# Control_Board.net
KiCad netlist of a schematic drawn in EAGLE
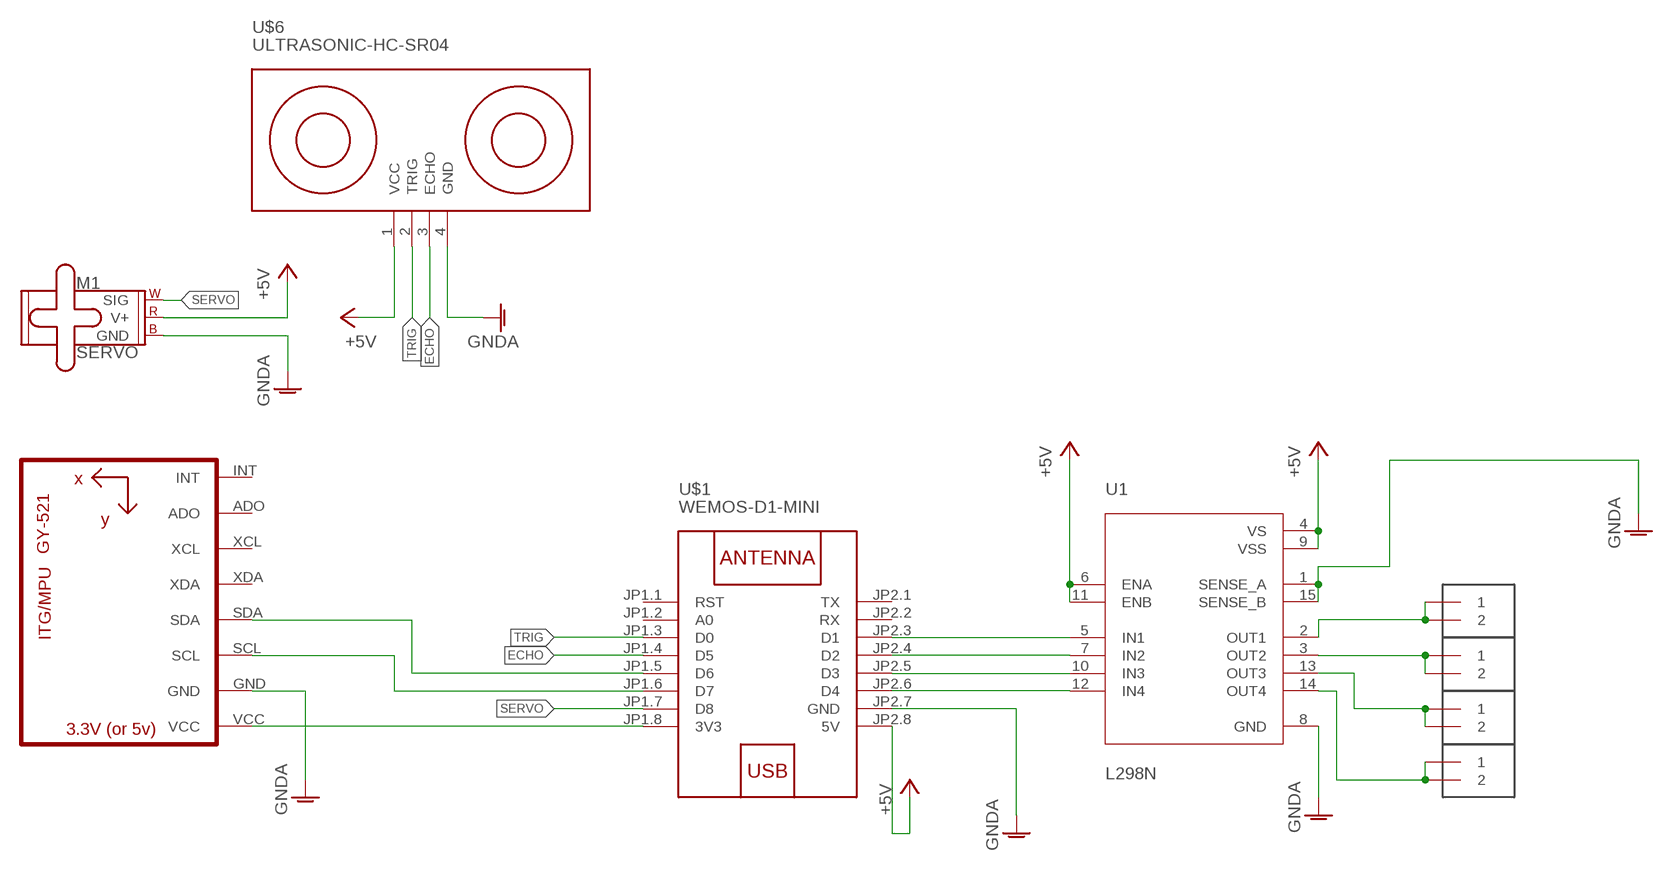
[diagram p0: schematic, sheet 1]

(export (version "E")
  (design (tool "Eeschema 10.0.6"))
  (components
    (comp (ref "M1")
      (value "SERVO")
      (footprint "eagle-import:1X03")
      (libsource (lib "eagle-import") (part "SERVO"))
    )
    (comp (ref "U$1")
      (value "WEMOS-D1-MINI")
      (footprint "eagle-import:WEMOS-D1-MINI")
      (libsource (lib "eagle-import") (part "WEMOS-D1-MINI"))
    )
    (comp (ref "U$2")
      (value "TERMINAL_2P")
      (footprint "eagle-import:KF301-2P")
      (libsource (lib "eagle-import") (part "TERMINAL_2P"))
    )
    (comp (ref "U$3")
      (value "TERMINAL_2P")
      (footprint "eagle-import:KF301-2P")
      (libsource (lib "eagle-import") (part "TERMINAL_2P"))
    )
    (comp (ref "U$4")
      (value "TERMINAL_2P")
      (footprint "eagle-import:KF301-2P")
      (libsource (lib "eagle-import") (part "TERMINAL_2P"))
    )
    (comp (ref "U$5")
      (value "TERMINAL_2P")
      (footprint "eagle-import:KF301-2P")
      (libsource (lib "eagle-import") (part "TERMINAL_2P"))
    )
    (comp (ref "U$6")
      (value "ULTRASONIC-HC-SR04")
      (footprint "eagle-import:ULTRASONIC-HC-SR04")
      (libsource (lib "eagle-import") (part "ULTRASONIC-HC-SR04"))
    )
    (comp (ref "U1")
      (value "L298N")
      (footprint "eagle-import:TO127P2020X500X2100-15")
      (fields (field (name "MF") "STMicroelectronics"))
      (libsource (lib "eagle-import") (part "L298N"))
    )
    (comp (ref "U2")
      (value "GY-521MPU6050")
      (footprint "eagle-import:GY-521")
      (libsource (lib "eagle-import") (part "GY-521MPU6050"))
    )
  )
  (nets
    (net (code "1") (name "+5V") (class "Default")
      (node (ref "M1") (pin "2") (pinfunction "V+_2") (pintype "bidirectional"))
      (node (ref "U$1") (pin "JP2.8") (pinfunction "5V_JP2.8") (pintype "power_in"))
      (node (ref "U$6") (pin "1") (pinfunction "VCC_1") (pintype "power_in"))
      (node (ref "U1") (pin "11") (pinfunction "ENB_11") (pintype "input"))
      (node (ref "U1") (pin "4") (pinfunction "VS_4") (pintype "power_in"))
      (node (ref "U1") (pin "6") (pinfunction "ENA_6") (pintype "input"))
      (node (ref "U1") (pin "9") (pinfunction "VSS_9") (pintype "input"))
    )
    (net (code "2") (name "ECHO") (class "Default")
      (node (ref "U$1") (pin "JP1.4") (pinfunction "D5_JP1.4") (pintype "bidirectional"))
      (node (ref "U$6") (pin "3") (pinfunction "ECHO_3") (pintype "output"))
    )
    (net (code "3") (name "GNDA") (class "Default")
      (node (ref "M1") (pin "3") (pinfunction "GND_3") (pintype "bidirectional"))
      (node (ref "U$1") (pin "JP2.7") (pinfunction "GND_JP2.7") (pintype "power_in"))
      (node (ref "U$6") (pin "4") (pinfunction "GND_4") (pintype "power_in"))
      (node (ref "U1") (pin "1") (pinfunction "SENSE_A_1") (pintype "passive"))
      (node (ref "U1") (pin "15") (pinfunction "SENSE_B_15") (pintype "passive"))
      (node (ref "U1") (pin "8") (pinfunction "GND_8") (pintype "power_in"))
      (node (ref "U2") (pin "GND") (pinfunction "GND_GND") (pintype "bidirectional"))
    )
    (net (code "4") (name "Net-(U$1-3V3)") (class "Default")
      (node (ref "U$1") (pin "JP1.8") (pinfunction "3V3_JP1.8") (pintype "power_in"))
      (node (ref "U2") (pin "VCC") (pinfunction "VCC_VCC") (pintype "bidirectional"))
    )
    (net (code "5") (name "Net-(U$1-D1)") (class "Default")
      (node (ref "U$1") (pin "JP2.3") (pinfunction "D1_JP2.3") (pintype "bidirectional"))
      (node (ref "U1") (pin "5") (pinfunction "IN1_5") (pintype "input"))
    )
    (net (code "6") (name "Net-(U$1-D2)") (class "Default")
      (node (ref "U$1") (pin "JP2.4") (pinfunction "D2_JP2.4") (pintype "bidirectional"))
      (node (ref "U1") (pin "7") (pinfunction "IN2_7") (pintype "input"))
    )
    (net (code "7") (name "Net-(U$1-D3)") (class "Default")
      (node (ref "U$1") (pin "JP2.5") (pinfunction "D3_JP2.5") (pintype "bidirectional"))
      (node (ref "U1") (pin "10") (pinfunction "IN3_10") (pintype "input"))
    )
    (net (code "8") (name "Net-(U$1-D4)") (class "Default")
      (node (ref "U$1") (pin "JP2.6") (pinfunction "D4_JP2.6") (pintype "bidirectional"))
      (node (ref "U1") (pin "12") (pinfunction "IN4_12") (pintype "input"))
    )
    (net (code "9") (name "Net-(U$1-D6)") (class "Default")
      (node (ref "U$1") (pin "JP1.5") (pinfunction "D6_JP1.5") (pintype "bidirectional"))
      (node (ref "U2") (pin "SDA") (pinfunction "SDA_SDA") (pintype "bidirectional"))
    )
    (net (code "10") (name "Net-(U$1-D7)") (class "Default")
      (node (ref "U$1") (pin "JP1.6") (pinfunction "D7_JP1.6") (pintype "bidirectional"))
      (node (ref "U2") (pin "SCL") (pinfunction "SCL_SCL") (pintype "bidirectional"))
    )
    (net (code "11") (name "Net-(U1-OUT1)") (class "Default")
      (node (ref "U$2") (pin "1") (pinfunction "1_1") (pintype "bidirectional"))
      (node (ref "U$2") (pin "2") (pinfunction "2_2") (pintype "bidirectional"))
      (node (ref "U1") (pin "2") (pinfunction "OUT1_2") (pintype "output"))
    )
    (net (code "12") (name "Net-(U1-OUT2)") (class "Default")
      (node (ref "U$3") (pin "1") (pinfunction "1_1") (pintype "bidirectional"))
      (node (ref "U$3") (pin "2") (pinfunction "2_2") (pintype "bidirectional"))
      (node (ref "U1") (pin "3") (pinfunction "OUT2_3") (pintype "output"))
    )
    (net (code "13") (name "Net-(U1-OUT3)") (class "Default")
      (node (ref "U$4") (pin "1") (pinfunction "1_1") (pintype "bidirectional"))
      (node (ref "U$4") (pin "2") (pinfunction "2_2") (pintype "bidirectional"))
      (node (ref "U1") (pin "13") (pinfunction "OUT3_13") (pintype "output"))
    )
    (net (code "14") (name "Net-(U1-OUT4)") (class "Default")
      (node (ref "U$5") (pin "1") (pinfunction "1_1") (pintype "bidirectional"))
      (node (ref "U$5") (pin "2") (pinfunction "2_2") (pintype "bidirectional"))
      (node (ref "U1") (pin "14") (pinfunction "OUT4_14") (pintype "output"))
    )
    (net (code "15") (name "SERVO") (class "Default")
      (node (ref "M1") (pin "1") (pinfunction "SIG_1") (pintype "bidirectional"))
      (node (ref "U$1") (pin "JP1.7") (pinfunction "D8_JP1.7") (pintype "bidirectional"))
    )
    (net (code "16") (name "TRIG") (class "Default")
      (node (ref "U$1") (pin "JP1.3") (pinfunction "D0_JP1.3") (pintype "bidirectional"))
      (node (ref "U$6") (pin "2") (pinfunction "TRIG_2") (pintype "input"))
    )
    (net (code "17") (name "unconnected-(U$1-A0-PadJP1.2)") (class "Default")
      (node (ref "U$1") (pin "JP1.2") (pinfunction "A0_JP1.2") (pintype "bidirectional"))
    )
    (net (code "18") (name "unconnected-(U$1-RST-PadJP1.1)") (class "Default")
      (node (ref "U$1") (pin "JP1.1") (pinfunction "RST_JP1.1") (pintype "bidirectional"))
    )
    (net (code "19") (name "unconnected-(U$1-RX-PadJP2.2)") (class "Default")
      (node (ref "U$1") (pin "JP2.2") (pinfunction "RX_JP2.2") (pintype "bidirectional"))
    )
    (net (code "20") (name "unconnected-(U$1-TX-PadJP2.1)") (class "Default")
      (node (ref "U$1") (pin "JP2.1") (pinfunction "TX_JP2.1") (pintype "bidirectional"))
    )
    (net (code "21") (name "unconnected-(U2-PadADO)") (class "Default")
      (node (ref "U2") (pin "ADO") (pinfunction "ADO_ADO") (pintype "bidirectional"))
    )
    (net (code "22") (name "unconnected-(U2-PadINT)") (class "Default")
      (node (ref "U2") (pin "INT") (pinfunction "INT_INT") (pintype "bidirectional"))
    )
    (net (code "23") (name "unconnected-(U2-PadXCL)") (class "Default")
      (node (ref "U2") (pin "XCL") (pinfunction "XCL_XCL") (pintype "bidirectional"))
    )
    (net (code "24") (name "unconnected-(U2-PadXDA)") (class "Default")
      (node (ref "U2") (pin "XDA") (pinfunction "XDA_XDA") (pintype "bidirectional"))
    )
  )
)
